# sidefacedraft3.net
KiCad netlist of a schematic drawn in EAGLE
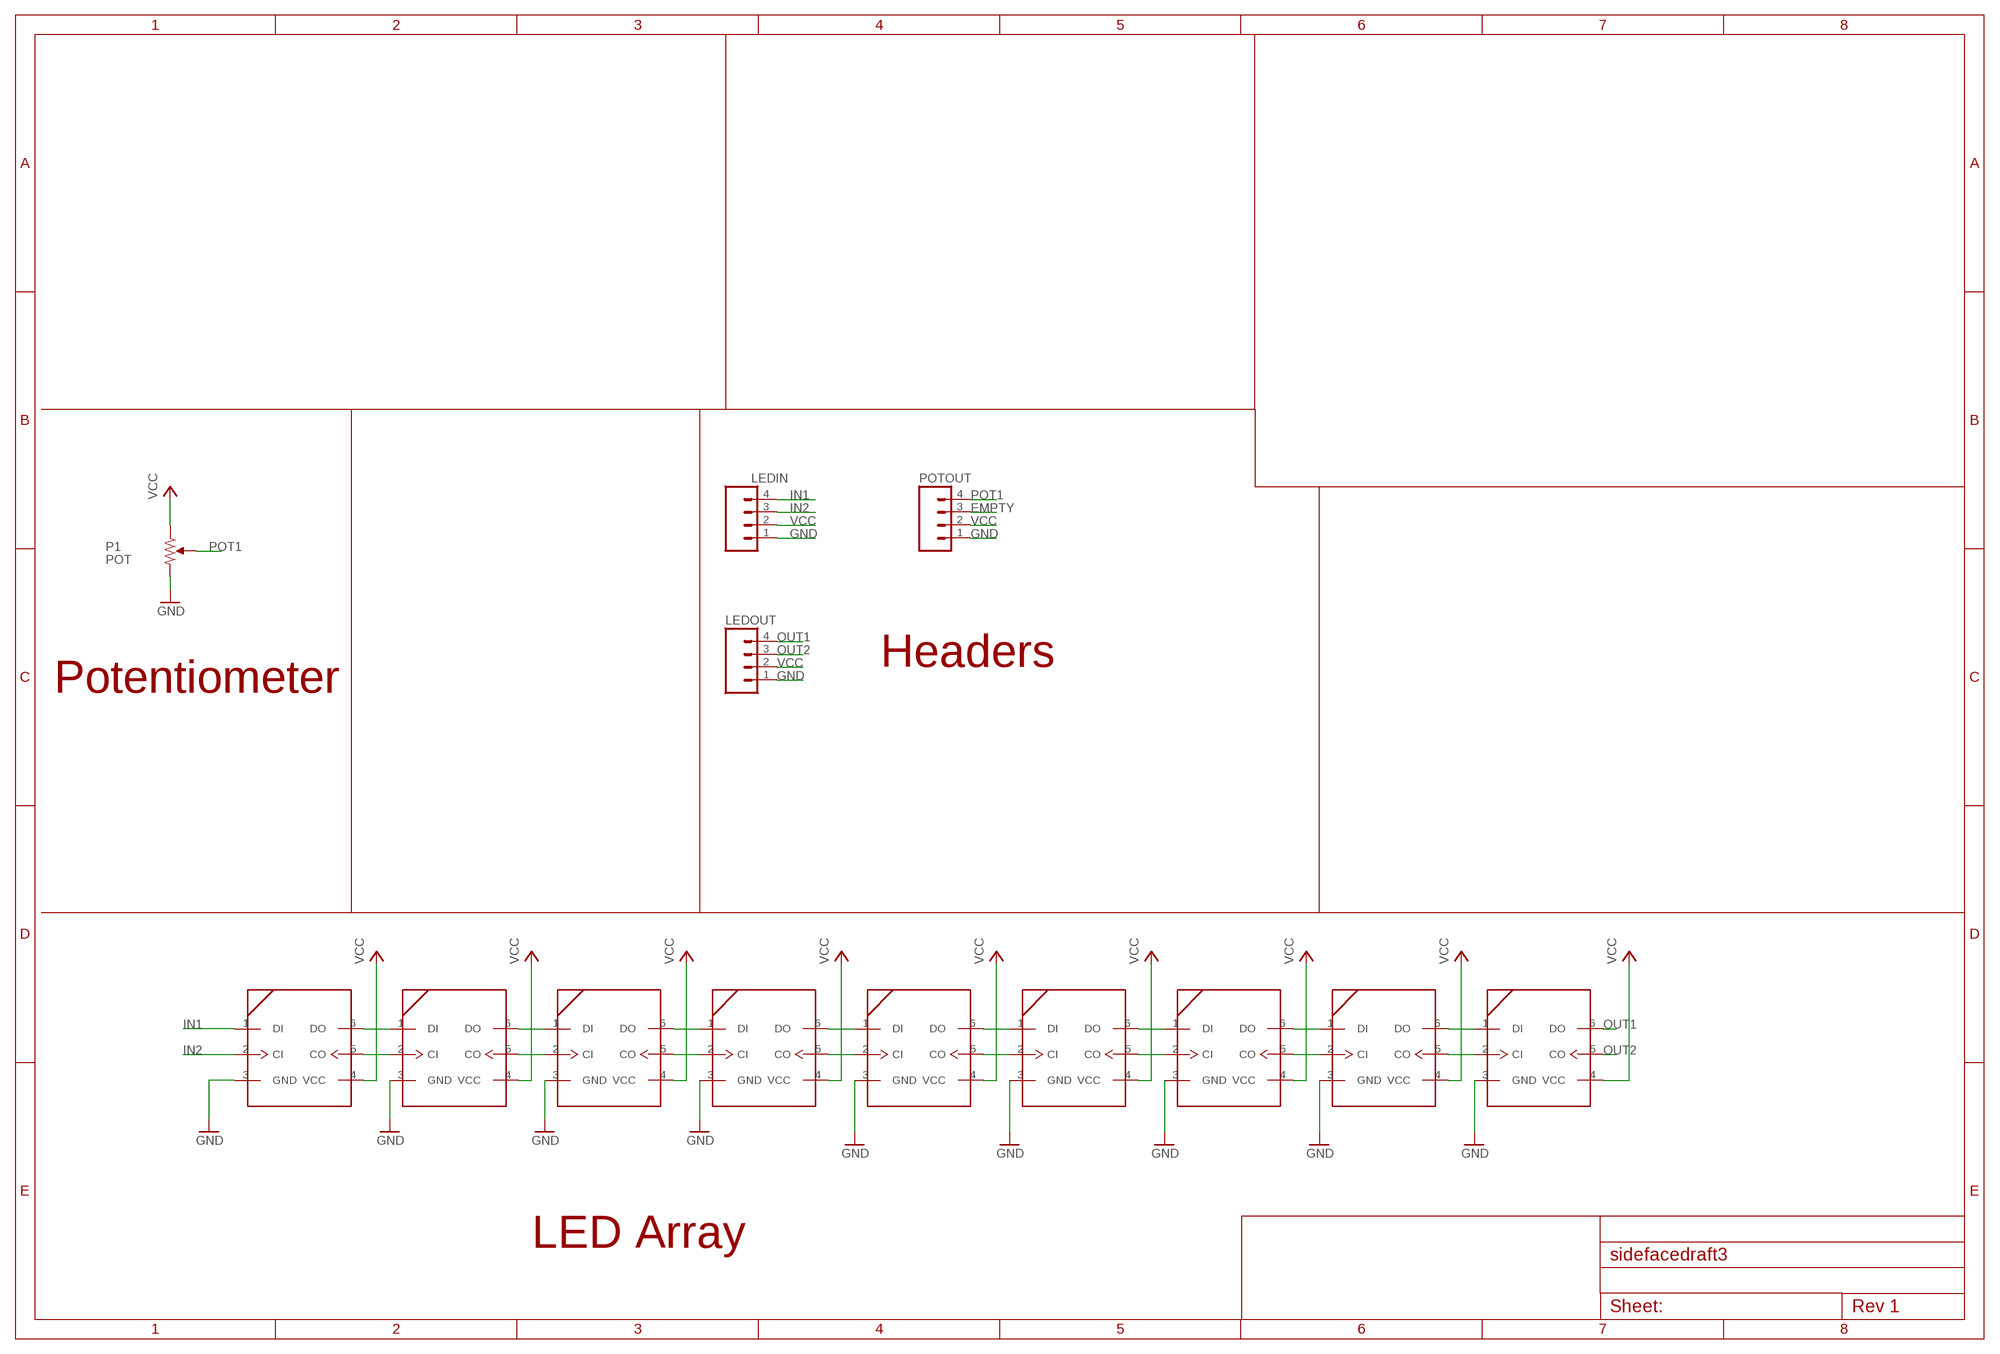
[diagram p0: schematic, sheet 1]

(export (version "E")
  (design (tool "Eeschema 10.0.6"))
  (components
    (comp (ref "LED1")
      (value "APA102")
      (footprint "eagle-import:5050")
      (libsource (lib "eagle-import") (part "APA102"))
    )
    (comp (ref "LED2")
      (value "APA102")
      (footprint "eagle-import:5050")
      (libsource (lib "eagle-import") (part "APA102"))
    )
    (comp (ref "LED3")
      (value "APA102")
      (footprint "eagle-import:5050")
      (libsource (lib "eagle-import") (part "APA102"))
    )
    (comp (ref "LED4")
      (value "APA102")
      (footprint "eagle-import:5050")
      (libsource (lib "eagle-import") (part "APA102"))
    )
    (comp (ref "LED5")
      (value "APA102")
      (footprint "eagle-import:5050")
      (libsource (lib "eagle-import") (part "APA102"))
    )
    (comp (ref "LED6")
      (value "APA102")
      (footprint "eagle-import:5050")
      (libsource (lib "eagle-import") (part "APA102"))
    )
    (comp (ref "LED7")
      (value "APA102")
      (footprint "eagle-import:5050")
      (libsource (lib "eagle-import") (part "APA102"))
    )
    (comp (ref "LED8")
      (value "APA102")
      (footprint "eagle-import:5050")
      (libsource (lib "eagle-import") (part "APA102"))
    )
    (comp (ref "LED9")
      (value "APA102")
      (footprint "eagle-import:5050")
      (libsource (lib "eagle-import") (part "APA102"))
    )
    (comp (ref "LEDIN")
      (value "M04LOCK")
      (footprint "eagle-import:1X04_LOCK")
      (libsource (lib "eagle-import") (part "M04LOCK"))
    )
    (comp (ref "LEDOUT")
      (value "M04LOCK")
      (footprint "eagle-import:1X04_LOCK")
      (libsource (lib "eagle-import") (part "M04LOCK"))
    )
    (comp (ref "P1")
      (value "POT")
      (footprint "eagle-import:POT")
      (libsource (lib "eagle-import") (part "POT"))
    )
    (comp (ref "POTOUT")
      (value "M04LOCK")
      (footprint "eagle-import:1X04_LOCK")
      (libsource (lib "eagle-import") (part "M04LOCK"))
    )
  )
  (nets
    (net (code "1") (name "/EMPTY") (class "Default")
      (node (ref "POTOUT") (pin "3") (pinfunction "3_3") (pintype "passive"))
    )
    (net (code "2") (name "/IN1") (class "Default")
      (node (ref "LED1") (pin "1") (pinfunction "DI_1") (pintype "input"))
      (node (ref "LEDIN") (pin "4") (pinfunction "4_4") (pintype "passive"))
    )
    (net (code "3") (name "/IN2") (class "Default")
      (node (ref "LED1") (pin "2") (pinfunction "CI_2") (pintype "input"))
      (node (ref "LEDIN") (pin "3") (pinfunction "3_3") (pintype "passive"))
    )
    (net (code "4") (name "/OUT1") (class "Default")
      (node (ref "LED9") (pin "6") (pinfunction "DO_6") (pintype "output"))
      (node (ref "LEDOUT") (pin "4") (pinfunction "4_4") (pintype "passive"))
    )
    (net (code "5") (name "/OUT2") (class "Default")
      (node (ref "LED9") (pin "5") (pinfunction "CO_5") (pintype "output"))
      (node (ref "LEDOUT") (pin "3") (pinfunction "3_3") (pintype "passive"))
    )
    (net (code "6") (name "/POT1") (class "Default")
      (node (ref "P1") (pin "SIG") (pinfunction "S_SIG") (pintype "bidirectional"))
      (node (ref "POTOUT") (pin "4") (pinfunction "4_4") (pintype "passive"))
    )
    (net (code "7") (name "GND") (class "Default")
      (node (ref "LED1") (pin "3") (pinfunction "GND_3") (pintype "power_in"))
      (node (ref "LED2") (pin "3") (pinfunction "GND_3") (pintype "power_in"))
      (node (ref "LED3") (pin "3") (pinfunction "GND_3") (pintype "power_in"))
      (node (ref "LED4") (pin "3") (pinfunction "GND_3") (pintype "power_in"))
      (node (ref "LED5") (pin "3") (pinfunction "GND_3") (pintype "power_in"))
      (node (ref "LED6") (pin "3") (pinfunction "GND_3") (pintype "power_in"))
      (node (ref "LED7") (pin "3") (pinfunction "GND_3") (pintype "power_in"))
      (node (ref "LED8") (pin "3") (pinfunction "GND_3") (pintype "power_in"))
      (node (ref "LED9") (pin "3") (pinfunction "GND_3") (pintype "power_in"))
      (node (ref "LEDIN") (pin "1") (pinfunction "1_1") (pintype "passive"))
      (node (ref "LEDOUT") (pin "1") (pinfunction "1_1") (pintype "passive"))
      (node (ref "P1") (pin "GND") (pinfunction "CW_GND") (pintype "passive"))
      (node (ref "POTOUT") (pin "1") (pinfunction "1_1") (pintype "passive"))
    )
    (net (code "8") (name "Net-(LED1-CO)") (class "Default")
      (node (ref "LED1") (pin "5") (pinfunction "CO_5") (pintype "output"))
      (node (ref "LED2") (pin "2") (pinfunction "CI_2") (pintype "input"))
    )
    (net (code "9") (name "Net-(LED1-DO)") (class "Default")
      (node (ref "LED1") (pin "6") (pinfunction "DO_6") (pintype "output"))
      (node (ref "LED2") (pin "1") (pinfunction "DI_1") (pintype "input"))
    )
    (net (code "10") (name "Net-(LED2-CO)") (class "Default")
      (node (ref "LED2") (pin "5") (pinfunction "CO_5") (pintype "output"))
      (node (ref "LED3") (pin "2") (pinfunction "CI_2") (pintype "input"))
    )
    (net (code "11") (name "Net-(LED2-DO)") (class "Default")
      (node (ref "LED2") (pin "6") (pinfunction "DO_6") (pintype "output"))
      (node (ref "LED3") (pin "1") (pinfunction "DI_1") (pintype "input"))
    )
    (net (code "12") (name "Net-(LED3-CO)") (class "Default")
      (node (ref "LED3") (pin "5") (pinfunction "CO_5") (pintype "output"))
      (node (ref "LED4") (pin "2") (pinfunction "CI_2") (pintype "input"))
    )
    (net (code "13") (name "Net-(LED3-DO)") (class "Default")
      (node (ref "LED3") (pin "6") (pinfunction "DO_6") (pintype "output"))
      (node (ref "LED4") (pin "1") (pinfunction "DI_1") (pintype "input"))
    )
    (net (code "14") (name "Net-(LED4-CO)") (class "Default")
      (node (ref "LED4") (pin "5") (pinfunction "CO_5") (pintype "output"))
      (node (ref "LED5") (pin "2") (pinfunction "CI_2") (pintype "input"))
    )
    (net (code "15") (name "Net-(LED4-DO)") (class "Default")
      (node (ref "LED4") (pin "6") (pinfunction "DO_6") (pintype "output"))
      (node (ref "LED5") (pin "1") (pinfunction "DI_1") (pintype "input"))
    )
    (net (code "16") (name "Net-(LED5-CO)") (class "Default")
      (node (ref "LED5") (pin "5") (pinfunction "CO_5") (pintype "output"))
      (node (ref "LED6") (pin "2") (pinfunction "CI_2") (pintype "input"))
    )
    (net (code "17") (name "Net-(LED5-DO)") (class "Default")
      (node (ref "LED5") (pin "6") (pinfunction "DO_6") (pintype "output"))
      (node (ref "LED6") (pin "1") (pinfunction "DI_1") (pintype "input"))
    )
    (net (code "18") (name "Net-(LED6-CO)") (class "Default")
      (node (ref "LED6") (pin "5") (pinfunction "CO_5") (pintype "output"))
      (node (ref "LED7") (pin "2") (pinfunction "CI_2") (pintype "input"))
    )
    (net (code "19") (name "Net-(LED6-DO)") (class "Default")
      (node (ref "LED6") (pin "6") (pinfunction "DO_6") (pintype "output"))
      (node (ref "LED7") (pin "1") (pinfunction "DI_1") (pintype "input"))
    )
    (net (code "20") (name "Net-(LED7-CO)") (class "Default")
      (node (ref "LED7") (pin "5") (pinfunction "CO_5") (pintype "output"))
      (node (ref "LED8") (pin "2") (pinfunction "CI_2") (pintype "input"))
    )
    (net (code "21") (name "Net-(LED7-DO)") (class "Default")
      (node (ref "LED7") (pin "6") (pinfunction "DO_6") (pintype "output"))
      (node (ref "LED8") (pin "1") (pinfunction "DI_1") (pintype "input"))
    )
    (net (code "22") (name "Net-(LED8-CO)") (class "Default")
      (node (ref "LED8") (pin "5") (pinfunction "CO_5") (pintype "output"))
      (node (ref "LED9") (pin "2") (pinfunction "CI_2") (pintype "input"))
    )
    (net (code "23") (name "Net-(LED8-DO)") (class "Default")
      (node (ref "LED8") (pin "6") (pinfunction "DO_6") (pintype "output"))
      (node (ref "LED9") (pin "1") (pinfunction "DI_1") (pintype "input"))
    )
    (net (code "24") (name "VCC") (class "Default")
      (node (ref "LED1") (pin "4") (pinfunction "VCC_4") (pintype "power_in"))
      (node (ref "LED2") (pin "4") (pinfunction "VCC_4") (pintype "power_in"))
      (node (ref "LED3") (pin "4") (pinfunction "VCC_4") (pintype "power_in"))
      (node (ref "LED4") (pin "4") (pinfunction "VCC_4") (pintype "power_in"))
      (node (ref "LED5") (pin "4") (pinfunction "VCC_4") (pintype "power_in"))
      (node (ref "LED6") (pin "4") (pinfunction "VCC_4") (pintype "power_in"))
      (node (ref "LED7") (pin "4") (pinfunction "VCC_4") (pintype "power_in"))
      (node (ref "LED8") (pin "4") (pinfunction "VCC_4") (pintype "power_in"))
      (node (ref "LED9") (pin "4") (pinfunction "VCC_4") (pintype "power_in"))
      (node (ref "LEDIN") (pin "2") (pinfunction "2_2") (pintype "passive"))
      (node (ref "LEDOUT") (pin "2") (pinfunction "2_2") (pintype "passive"))
      (node (ref "P1") (pin "VDD") (pinfunction "CCW_VDD") (pintype "passive"))
      (node (ref "POTOUT") (pin "2") (pinfunction "2_2") (pintype "passive"))
    )
  )
)
